# R_Box.net
KiCad netlist of a schematic drawn in Altium Designer
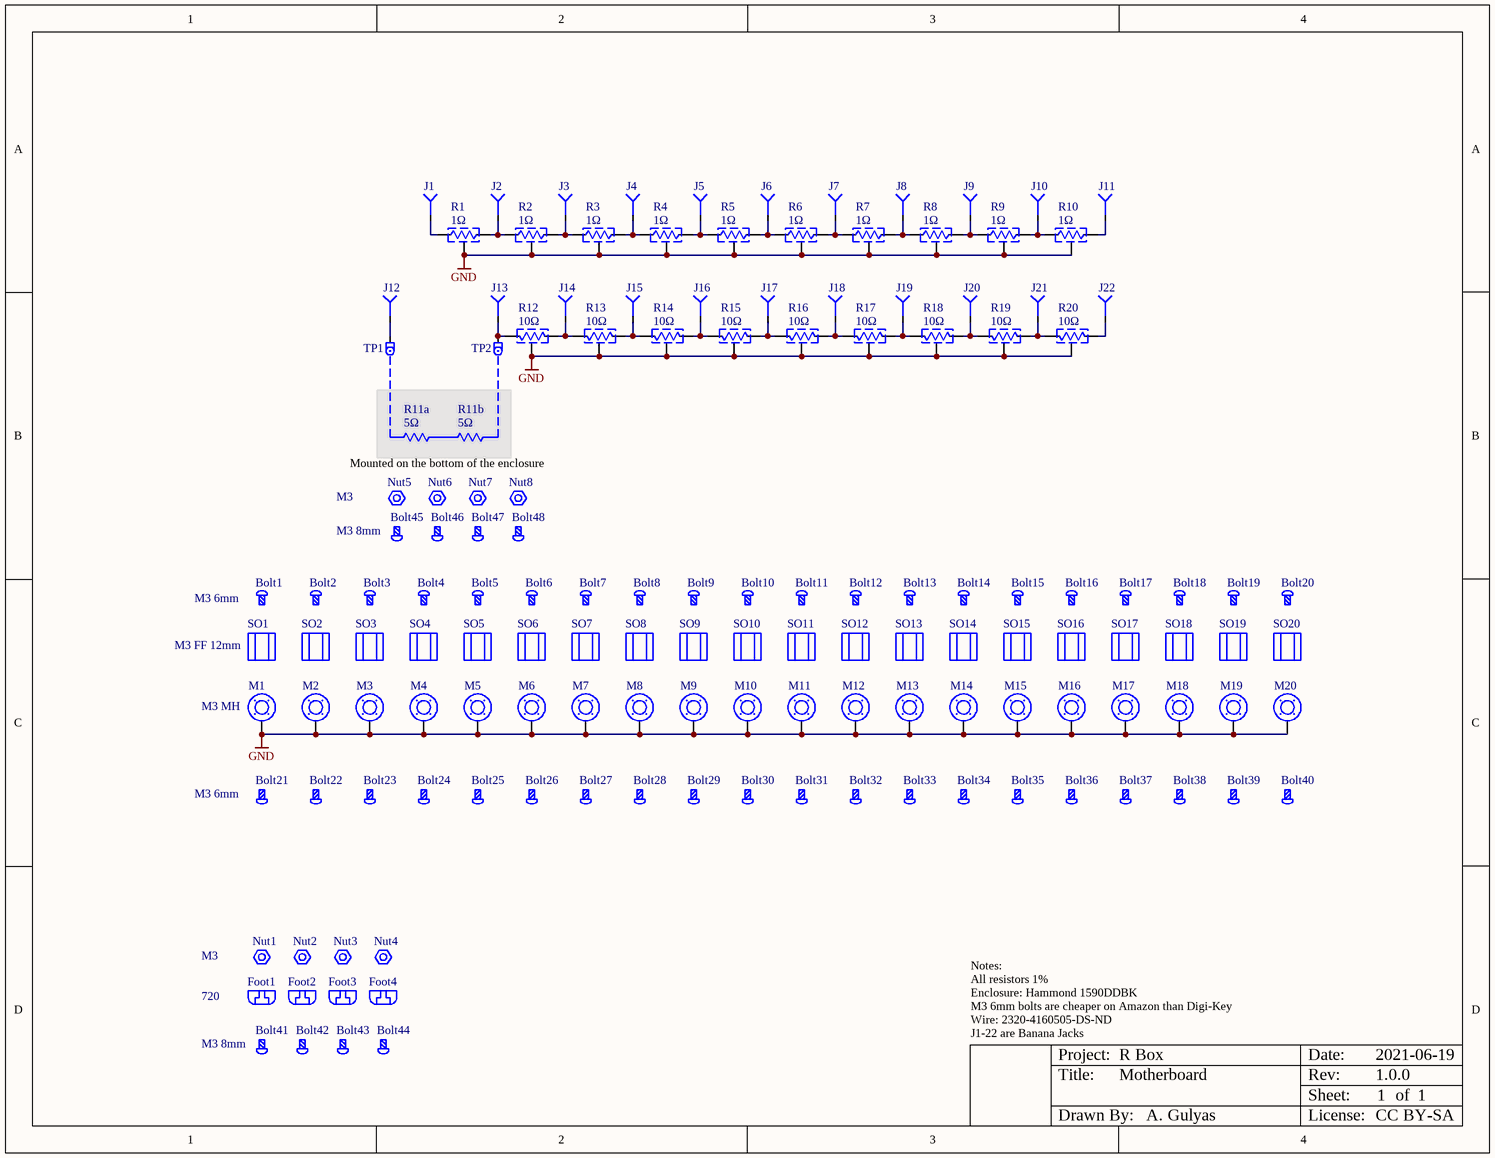
[diagram p0: R Box.SchDoc]

(export (version "E")
  (design (tool "Eeschema 10.0.6"))
  (components
    (comp (ref "Bolt1")
      (value "M3 6mm")
      (footprint "Mech - Bolt - M3 - 6mm")
      (description "MACH SCREW PAN HEAD PHILLIPS M3")
      (fields (field (name "MFG") "APM Hexseal"))
      (libsource (lib "Public Library") (part "Mech - Bolt - M3 - 6mm"))
    )
    (comp (ref "Bolt2")
      (value "M3 6mm")
      (footprint "Mech - Bolt - M3 - 6mm")
      (description "MACH SCREW PAN HEAD PHILLIPS M3")
      (fields (field (name "MFG") "APM Hexseal"))
      (libsource (lib "Public Library") (part "Mech - Bolt - M3 - 6mm"))
    )
    (comp (ref "Bolt3")
      (value "M3 6mm")
      (footprint "Mech - Bolt - M3 - 6mm")
      (description "MACH SCREW PAN HEAD PHILLIPS M3")
      (fields (field (name "MFG") "APM Hexseal"))
      (libsource (lib "Public Library") (part "Mech - Bolt - M3 - 6mm"))
    )
    (comp (ref "Bolt4")
      (value "M3 6mm")
      (footprint "Mech - Bolt - M3 - 6mm")
      (description "MACH SCREW PAN HEAD PHILLIPS M3")
      (fields (field (name "MFG") "APM Hexseal"))
      (libsource (lib "Public Library") (part "Mech - Bolt - M3 - 6mm"))
    )
    (comp (ref "Bolt5")
      (value "M3 6mm")
      (footprint "Mech - Bolt - M3 - 6mm")
      (description "MACH SCREW PAN HEAD PHILLIPS M3")
      (fields (field (name "MFG") "APM Hexseal"))
      (libsource (lib "Public Library") (part "Mech - Bolt - M3 - 6mm"))
    )
    (comp (ref "Bolt6")
      (value "M3 6mm")
      (footprint "Mech - Bolt - M3 - 6mm")
      (description "MACH SCREW PAN HEAD PHILLIPS M3")
      (fields (field (name "MFG") "APM Hexseal"))
      (libsource (lib "Public Library") (part "Mech - Bolt - M3 - 6mm"))
    )
    (comp (ref "Bolt7")
      (value "M3 6mm")
      (footprint "Mech - Bolt - M3 - 6mm")
      (description "MACH SCREW PAN HEAD PHILLIPS M3")
      (fields (field (name "MFG") "APM Hexseal"))
      (libsource (lib "Public Library") (part "Mech - Bolt - M3 - 6mm"))
    )
    (comp (ref "Bolt8")
      (value "M3 6mm")
      (footprint "Mech - Bolt - M3 - 6mm")
      (description "MACH SCREW PAN HEAD PHILLIPS M3")
      (fields (field (name "MFG") "APM Hexseal"))
      (libsource (lib "Public Library") (part "Mech - Bolt - M3 - 6mm"))
    )
    (comp (ref "Bolt9")
      (value "M3 6mm")
      (footprint "Mech - Bolt - M3 - 6mm")
      (description "MACH SCREW PAN HEAD PHILLIPS M3")
      (fields (field (name "MFG") "APM Hexseal"))
      (libsource (lib "Public Library") (part "Mech - Bolt - M3 - 6mm"))
    )
    (comp (ref "Bolt10")
      (value "M3 6mm")
      (footprint "Mech - Bolt - M3 - 6mm")
      (description "MACH SCREW PAN HEAD PHILLIPS M3")
      (fields (field (name "MFG") "APM Hexseal"))
      (libsource (lib "Public Library") (part "Mech - Bolt - M3 - 6mm"))
    )
    (comp (ref "Bolt11")
      (value "M3 6mm")
      (footprint "Mech - Bolt - M3 - 6mm")
      (description "MACH SCREW PAN HEAD PHILLIPS M3")
      (fields (field (name "MFG") "APM Hexseal"))
      (libsource (lib "Public Library") (part "Mech - Bolt - M3 - 6mm"))
    )
    (comp (ref "Bolt12")
      (value "M3 6mm")
      (footprint "Mech - Bolt - M3 - 6mm")
      (description "MACH SCREW PAN HEAD PHILLIPS M3")
      (fields (field (name "MFG") "APM Hexseal"))
      (libsource (lib "Public Library") (part "Mech - Bolt - M3 - 6mm"))
    )
    (comp (ref "Bolt13")
      (value "M3 6mm")
      (footprint "Mech - Bolt - M3 - 6mm")
      (description "MACH SCREW PAN HEAD PHILLIPS M3")
      (fields (field (name "MFG") "APM Hexseal"))
      (libsource (lib "Public Library") (part "Mech - Bolt - M3 - 6mm"))
    )
    (comp (ref "Bolt14")
      (value "M3 6mm")
      (footprint "Mech - Bolt - M3 - 6mm")
      (description "MACH SCREW PAN HEAD PHILLIPS M3")
      (fields (field (name "MFG") "APM Hexseal"))
      (libsource (lib "Public Library") (part "Mech - Bolt - M3 - 6mm"))
    )
    (comp (ref "Bolt15")
      (value "M3 6mm")
      (footprint "Mech - Bolt - M3 - 6mm")
      (description "MACH SCREW PAN HEAD PHILLIPS M3")
      (fields (field (name "MFG") "APM Hexseal"))
      (libsource (lib "Public Library") (part "Mech - Bolt - M3 - 6mm"))
    )
    (comp (ref "Bolt16")
      (value "M3 6mm")
      (footprint "Mech - Bolt - M3 - 6mm")
      (description "MACH SCREW PAN HEAD PHILLIPS M3")
      (fields (field (name "MFG") "APM Hexseal"))
      (libsource (lib "Public Library") (part "Mech - Bolt - M3 - 6mm"))
    )
    (comp (ref "Bolt17")
      (value "M3 6mm")
      (footprint "Mech - Bolt - M3 - 6mm")
      (description "MACH SCREW PAN HEAD PHILLIPS M3")
      (fields (field (name "MFG") "APM Hexseal"))
      (libsource (lib "Public Library") (part "Mech - Bolt - M3 - 6mm"))
    )
    (comp (ref "Bolt18")
      (value "M3 6mm")
      (footprint "Mech - Bolt - M3 - 6mm")
      (description "MACH SCREW PAN HEAD PHILLIPS M3")
      (fields (field (name "MFG") "APM Hexseal"))
      (libsource (lib "Public Library") (part "Mech - Bolt - M3 - 6mm"))
    )
    (comp (ref "Bolt19")
      (value "M3 6mm")
      (footprint "Mech - Bolt - M3 - 6mm")
      (description "MACH SCREW PAN HEAD PHILLIPS M3")
      (fields (field (name "MFG") "APM Hexseal"))
      (libsource (lib "Public Library") (part "Mech - Bolt - M3 - 6mm"))
    )
    (comp (ref "Bolt20")
      (value "M3 6mm")
      (footprint "Mech - Bolt - M3 - 6mm")
      (description "MACH SCREW PAN HEAD PHILLIPS M3")
      (fields (field (name "MFG") "APM Hexseal"))
      (libsource (lib "Public Library") (part "Mech - Bolt - M3 - 6mm"))
    )
    (comp (ref "Bolt21")
      (value "M3 6mm")
      (footprint "Mech - Bolt - M3 - 6mm - back")
      (description "MACH SCREW PAN HEAD PHILLIPS M3")
      (fields (field (name "MFG") "APM Hexseal"))
      (libsource (lib "") (part "Mech - Bolt - M3 - 6mm_1"))
    )
    (comp (ref "Bolt22")
      (value "M3 6mm")
      (footprint "Mech - Bolt - M3 - 6mm - back")
      (description "MACH SCREW PAN HEAD PHILLIPS M3")
      (fields (field (name "MFG") "APM Hexseal"))
      (libsource (lib "") (part "Mech - Bolt - M3 - 6mm_1"))
    )
    (comp (ref "Bolt23")
      (value "M3 6mm")
      (footprint "Mech - Bolt - M3 - 6mm - back")
      (description "MACH SCREW PAN HEAD PHILLIPS M3")
      (fields (field (name "MFG") "APM Hexseal"))
      (libsource (lib "") (part "Mech - Bolt - M3 - 6mm_1"))
    )
    (comp (ref "Bolt24")
      (value "M3 6mm")
      (footprint "Mech - Bolt - M3 - 6mm - back")
      (description "MACH SCREW PAN HEAD PHILLIPS M3")
      (fields (field (name "MFG") "APM Hexseal"))
      (libsource (lib "") (part "Mech - Bolt - M3 - 6mm_1"))
    )
    (comp (ref "Bolt25")
      (value "M3 6mm")
      (footprint "Mech - Bolt - M3 - 6mm - back")
      (description "MACH SCREW PAN HEAD PHILLIPS M3")
      (fields (field (name "MFG") "APM Hexseal"))
      (libsource (lib "") (part "Mech - Bolt - M3 - 6mm_1"))
    )
    (comp (ref "Bolt26")
      (value "M3 6mm")
      (footprint "Mech - Bolt - M3 - 6mm - back")
      (description "MACH SCREW PAN HEAD PHILLIPS M3")
      (fields (field (name "MFG") "APM Hexseal"))
      (libsource (lib "") (part "Mech - Bolt - M3 - 6mm_1"))
    )
    (comp (ref "Bolt27")
      (value "M3 6mm")
      (footprint "Mech - Bolt - M3 - 6mm - back")
      (description "MACH SCREW PAN HEAD PHILLIPS M3")
      (fields (field (name "MFG") "APM Hexseal"))
      (libsource (lib "") (part "Mech - Bolt - M3 - 6mm_1"))
    )
    (comp (ref "Bolt28")
      (value "M3 6mm")
      (footprint "Mech - Bolt - M3 - 6mm - back")
      (description "MACH SCREW PAN HEAD PHILLIPS M3")
      (fields (field (name "MFG") "APM Hexseal"))
      (libsource (lib "") (part "Mech - Bolt - M3 - 6mm_1"))
    )
    (comp (ref "Bolt29")
      (value "M3 6mm")
      (footprint "Mech - Bolt - M3 - 6mm - back")
      (description "MACH SCREW PAN HEAD PHILLIPS M3")
      (fields (field (name "MFG") "APM Hexseal"))
      (libsource (lib "") (part "Mech - Bolt - M3 - 6mm_1"))
    )
    (comp (ref "Bolt30")
      (value "M3 6mm")
      (footprint "Mech - Bolt - M3 - 6mm - back")
      (description "MACH SCREW PAN HEAD PHILLIPS M3")
      (fields (field (name "MFG") "APM Hexseal"))
      (libsource (lib "") (part "Mech - Bolt - M3 - 6mm_1"))
    )
    (comp (ref "Bolt31")
      (value "M3 6mm")
      (footprint "Mech - Bolt - M3 - 6mm - back")
      (description "MACH SCREW PAN HEAD PHILLIPS M3")
      (fields (field (name "MFG") "APM Hexseal"))
      (libsource (lib "") (part "Mech - Bolt - M3 - 6mm_1"))
    )
    (comp (ref "Bolt32")
      (value "M3 6mm")
      (footprint "Mech - Bolt - M3 - 6mm - back")
      (description "MACH SCREW PAN HEAD PHILLIPS M3")
      (fields (field (name "MFG") "APM Hexseal"))
      (libsource (lib "") (part "Mech - Bolt - M3 - 6mm_1"))
    )
    (comp (ref "Bolt33")
      (value "M3 6mm")
      (footprint "Mech - Bolt - M3 - 6mm - back")
      (description "MACH SCREW PAN HEAD PHILLIPS M3")
      (fields (field (name "MFG") "APM Hexseal"))
      (libsource (lib "") (part "Mech - Bolt - M3 - 6mm_1"))
    )
    (comp (ref "Bolt34")
      (value "M3 6mm")
      (footprint "Mech - Bolt - M3 - 6mm - back")
      (description "MACH SCREW PAN HEAD PHILLIPS M3")
      (fields (field (name "MFG") "APM Hexseal"))
      (libsource (lib "") (part "Mech - Bolt - M3 - 6mm_1"))
    )
    (comp (ref "Bolt35")
      (value "M3 6mm")
      (footprint "Mech - Bolt - M3 - 6mm - back")
      (description "MACH SCREW PAN HEAD PHILLIPS M3")
      (fields (field (name "MFG") "APM Hexseal"))
      (libsource (lib "") (part "Mech - Bolt - M3 - 6mm_1"))
    )
    (comp (ref "Bolt36")
      (value "M3 6mm")
      (footprint "Mech - Bolt - M3 - 6mm - back")
      (description "MACH SCREW PAN HEAD PHILLIPS M3")
      (fields (field (name "MFG") "APM Hexseal"))
      (libsource (lib "") (part "Mech - Bolt - M3 - 6mm_1"))
    )
    (comp (ref "Bolt37")
      (value "M3 6mm")
      (footprint "Mech - Bolt - M3 - 6mm - back")
      (description "MACH SCREW PAN HEAD PHILLIPS M3")
      (fields (field (name "MFG") "APM Hexseal"))
      (libsource (lib "") (part "Mech - Bolt - M3 - 6mm_1"))
    )
    (comp (ref "Bolt38")
      (value "M3 6mm")
      (footprint "Mech - Bolt - M3 - 6mm - back")
      (description "MACH SCREW PAN HEAD PHILLIPS M3")
      (fields (field (name "MFG") "APM Hexseal"))
      (libsource (lib "") (part "Mech - Bolt - M3 - 6mm_1"))
    )
    (comp (ref "Bolt39")
      (value "M3 6mm")
      (footprint "Mech - Bolt - M3 - 6mm - back")
      (description "MACH SCREW PAN HEAD PHILLIPS M3")
      (fields (field (name "MFG") "APM Hexseal"))
      (libsource (lib "") (part "Mech - Bolt - M3 - 6mm_1"))
    )
    (comp (ref "Bolt40")
      (value "M3 6mm")
      (footprint "Mech - Bolt - M3 - 6mm - back")
      (description "MACH SCREW PAN HEAD PHILLIPS M3")
      (fields (field (name "MFG") "APM Hexseal"))
      (libsource (lib "") (part "Mech - Bolt - M3 - 6mm_1"))
    )
    (comp (ref "Bolt41")
      (value "M3 8mm")
      (footprint "Mech - Bolt - M3 - 8mm")
      (description "MACH SCREW PAN HEAD PHILLIPS M3")
      (fields (field (name "MFG") "B&F Fastener Supply"))
      (libsource (lib "Public Library") (part "Mech - Bolt - M3 - 8mm"))
    )
    (comp (ref "Bolt42")
      (value "M3 8mm")
      (footprint "Mech - Bolt - M3 - 8mm")
      (description "MACH SCREW PAN HEAD PHILLIPS M3")
      (fields (field (name "MFG") "B&F Fastener Supply"))
      (libsource (lib "Public Library") (part "Mech - Bolt - M3 - 8mm"))
    )
    (comp (ref "Bolt43")
      (value "M3 8mm")
      (footprint "Mech - Bolt - M3 - 8mm")
      (description "MACH SCREW PAN HEAD PHILLIPS M3")
      (fields (field (name "MFG") "B&F Fastener Supply"))
      (libsource (lib "Public Library") (part "Mech - Bolt - M3 - 8mm"))
    )
    (comp (ref "Bolt44")
      (value "M3 8mm")
      (footprint "Mech - Bolt - M3 - 8mm")
      (description "MACH SCREW PAN HEAD PHILLIPS M3")
      (fields (field (name "MFG") "B&F Fastener Supply"))
      (libsource (lib "Public Library") (part "Mech - Bolt - M3 - 8mm"))
    )
    (comp (ref "Bolt45")
      (value "M3 8mm")
      (footprint "Mech - Bolt - M3 - 8mm")
      (description "MACH SCREW PAN HEAD PHILLIPS M3")
      (fields (field (name "MFG") "B&F Fastener Supply"))
      (libsource (lib "Public Library") (part "Mech - Bolt - M3 - 8mm"))
    )
    (comp (ref "Bolt46")
      (value "M3 8mm")
      (footprint "Mech - Bolt - M3 - 8mm")
      (description "MACH SCREW PAN HEAD PHILLIPS M3")
      (fields (field (name "MFG") "B&F Fastener Supply"))
      (libsource (lib "Public Library") (part "Mech - Bolt - M3 - 8mm"))
    )
    (comp (ref "Bolt47")
      (value "M3 8mm")
      (footprint "Mech - Bolt - M3 - 8mm")
      (description "MACH SCREW PAN HEAD PHILLIPS M3")
      (fields (field (name "MFG") "B&F Fastener Supply"))
      (libsource (lib "Public Library") (part "Mech - Bolt - M3 - 8mm"))
    )
    (comp (ref "Bolt48")
      (value "M3 8mm")
      (footprint "Mech - Bolt - M3 - 8mm")
      (description "MACH SCREW PAN HEAD PHILLIPS M3")
      (fields (field (name "MFG") "B&F Fastener Supply"))
      (libsource (lib "Public Library") (part "Mech - Bolt - M3 - 8mm"))
    )
    (comp (ref "Foot1")
      (value "720")
      (footprint "Feet - M3 - PN720")
      (description "BUMPER CYLINDRICAL 0.5\" DIA BLK")
      (fields (field (name "MFG") "Keystone Electronics"))
      (libsource (lib "Public Library") (part "Feet - M3 - 720"))
    )
    (comp (ref "Foot2")
      (value "720")
      (footprint "Feet - M3 - PN720")
      (description "BUMPER CYLINDRICAL 0.5\" DIA BLK")
      (fields (field (name "MFG") "Keystone Electronics"))
      (libsource (lib "Public Library") (part "Feet - M3 - 720"))
    )
    (comp (ref "Foot3")
      (value "720")
      (footprint "Feet - M3 - PN720")
      (description "BUMPER CYLINDRICAL 0.5\" DIA BLK")
      (fields (field (name "MFG") "Keystone Electronics"))
      (libsource (lib "Public Library") (part "Feet - M3 - 720"))
    )
    (comp (ref "Foot4")
      (value "720")
      (footprint "Feet - M3 - PN720")
      (description "BUMPER CYLINDRICAL 0.5\" DIA BLK")
      (fields (field (name "MFG") "Keystone Electronics"))
      (libsource (lib "Public Library") (part "Feet - M3 - 720"))
    )
    (comp (ref "J1")
      (value "Banana")
      (footprint "J - Banana - 108-09xx series")
      (description "CONN BANANA JACK SLDR TABS GREEN")
      (fields (field (name "MFG") "Cinch Connectivity Solutions Johnson"))
      (libsource (lib "Public Library") (part "Jack - Banana - 108-0904-001"))
    )
    (comp (ref "J2")
      (value "Banana")
      (footprint "J - Banana - 108-09xx series")
      (description "CONN BANANA JACK SLDR TABS GREEN")
      (fields (field (name "MFG") "Cinch Connectivity Solutions Johnson"))
      (libsource (lib "Public Library") (part "Jack - Banana - 108-0904-001"))
    )
    (comp (ref "J3")
      (value "Banana")
      (footprint "J - Banana - 108-09xx series")
      (description "CONN BANANA JACK SLDR TABS GREEN")
      (fields (field (name "MFG") "Cinch Connectivity Solutions Johnson"))
      (libsource (lib "Public Library") (part "Jack - Banana - 108-0904-001"))
    )
    (comp (ref "J4")
      (value "Banana")
      (footprint "J - Banana - 108-09xx series")
      (description "CONN BANANA JACK SLDR TABS GREEN")
      (fields (field (name "MFG") "Cinch Connectivity Solutions Johnson"))
      (libsource (lib "Public Library") (part "Jack - Banana - 108-0904-001"))
    )
    (comp (ref "J5")
      (value "Banana")
      (footprint "J - Banana - 108-09xx series")
      (description "CONN BANANA JACK SLDR TABS GREEN")
      (fields (field (name "MFG") "Cinch Connectivity Solutions Johnson"))
      (libsource (lib "Public Library") (part "Jack - Banana - 108-0904-001"))
    )
    (comp (ref "J6")
      (value "Banana")
      (footprint "J - Banana - 108-09xx series")
      (description "CONN BANANA JACK SLDR TABS GREEN")
      (fields (field (name "MFG") "Cinch Connectivity Solutions Johnson"))
      (libsource (lib "Public Library") (part "Jack - Banana - 108-0904-001"))
    )
    (comp (ref "J7")
      (value "Banana")
      (footprint "J - Banana - 108-09xx series")
      (description "CONN BANANA JACK SLDR TABS GREEN")
      (fields (field (name "MFG") "Cinch Connectivity Solutions Johnson"))
      (libsource (lib "Public Library") (part "Jack - Banana - 108-0904-001"))
    )
    (comp (ref "J8")
      (value "Banana")
      (footprint "J - Banana - 108-09xx series")
      (description "CONN BANANA JACK SLDR TABS GREEN")
      (fields (field (name "MFG") "Cinch Connectivity Solutions Johnson"))
      (libsource (lib "Public Library") (part "Jack - Banana - 108-0904-001"))
    )
    (comp (ref "J9")
      (value "Banana")
      (footprint "J - Banana - 108-09xx series")
      (description "CONN BANANA JACK SLDR TABS GREEN")
      (fields (field (name "MFG") "Cinch Connectivity Solutions Johnson"))
      (libsource (lib "Public Library") (part "Jack - Banana - 108-0904-001"))
    )
    (comp (ref "J10")
      (value "Banana")
      (footprint "J - Banana - 108-09xx series")
      (description "CONN BANANA JACK SLDR TABS GREEN")
      (fields (field (name "MFG") "Cinch Connectivity Solutions Johnson"))
      (libsource (lib "Public Library") (part "Jack - Banana - 108-0904-001"))
    )
    (comp (ref "J11")
      (value "Banana")
      (footprint "J - Banana - 108-09xx series")
      (description "CONN BANANA JACK SLDR TABS GREEN")
      (fields (field (name "MFG") "Cinch Connectivity Solutions Johnson"))
      (libsource (lib "Public Library") (part "Jack - Banana - 108-0904-001"))
    )
    (comp (ref "J12")
      (value "Banana")
      (footprint "J - Banana - 108-09xx series")
      (description "CONN BANANA JACK SLDR TABS GREEN")
      (fields (field (name "MFG") "Cinch Connectivity Solutions Johnson"))
      (libsource (lib "Public Library") (part "Jack - Banana - 108-0904-001"))
    )
    (comp (ref "J13")
      (value "Banana")
      (footprint "J - Banana - 108-09xx series")
      (description "CONN BANANA JACK SLDR TABS GREEN")
      (fields (field (name "MFG") "Cinch Connectivity Solutions Johnson"))
      (libsource (lib "Public Library") (part "Jack - Banana - 108-0904-001"))
    )
    (comp (ref "J14")
      (value "Banana")
      (footprint "J - Banana - 108-09xx series")
      (description "CONN BANANA JACK SLDR TABS GREEN")
      (fields (field (name "MFG") "Cinch Connectivity Solutions Johnson"))
      (libsource (lib "Public Library") (part "Jack - Banana - 108-0904-001"))
    )
    (comp (ref "J15")
      (value "Banana")
      (footprint "J - Banana - 108-09xx series")
      (description "CONN BANANA JACK SLDR TABS GREEN")
      (fields (field (name "MFG") "Cinch Connectivity Solutions Johnson"))
      (libsource (lib "Public Library") (part "Jack - Banana - 108-0904-001"))
    )
    (comp (ref "J16")
      (value "Banana")
      (footprint "J - Banana - 108-09xx series")
      (description "CONN BANANA JACK SLDR TABS GREEN")
      (fields (field (name "MFG") "Cinch Connectivity Solutions Johnson"))
      (libsource (lib "Public Library") (part "Jack - Banana - 108-0904-001"))
    )
    (comp (ref "J17")
      (value "Banana")
      (footprint "J - Banana - 108-09xx series")
      (description "CONN BANANA JACK SLDR TABS GREEN")
      (fields (field (name "MFG") "Cinch Connectivity Solutions Johnson"))
      (libsource (lib "Public Library") (part "Jack - Banana - 108-0904-001"))
    )
    (comp (ref "J18")
      (value "Banana")
      (footprint "J - Banana - 108-09xx series")
      (description "CONN BANANA JACK SLDR TABS GREEN")
      (fields (field (name "MFG") "Cinch Connectivity Solutions Johnson"))
      (libsource (lib "Public Library") (part "Jack - Banana - 108-0904-001"))
    )
    (comp (ref "J19")
      (value "Banana")
      (footprint "J - Banana - 108-09xx series")
      (description "CONN BANANA JACK SLDR TABS GREEN")
      (fields (field (name "MFG") "Cinch Connectivity Solutions Johnson"))
      (libsource (lib "Public Library") (part "Jack - Banana - 108-0904-001"))
    )
    (comp (ref "J20")
      (value "Banana")
      (footprint "J - Banana - 108-09xx series")
      (description "CONN BANANA JACK SLDR TABS GREEN")
      (fields (field (name "MFG") "Cinch Connectivity Solutions Johnson"))
      (libsource (lib "Public Library") (part "Jack - Banana - 108-0904-001"))
    )
    (comp (ref "J21")
      (value "Banana")
      (footprint "J - Banana - 108-09xx series")
      (description "CONN BANANA JACK SLDR TABS GREEN")
      (fields (field (name "MFG") "Cinch Connectivity Solutions Johnson"))
      (libsource (lib "Public Library") (part "Jack - Banana - 108-0904-001"))
    )
    (comp (ref "J22")
      (value "Banana")
      (footprint "J - Banana - 108-09xx series")
      (description "CONN BANANA JACK SLDR TABS GREEN")
      (fields (field (name "MFG") "Cinch Connectivity Solutions Johnson"))
      (libsource (lib "Public Library") (part "Jack - Banana - 108-0904-001"))
    )
    (comp (ref "M1")
      (value "M3 MH")
      (footprint "Bolt Hole - M3")
      (description "M3 Mounting Pad")
      (libsource (lib "Public Library") (part "Mech - Bolt Hole - M3"))
    )
    (comp (ref "M2")
      (value "M3 MH")
      (footprint "Bolt Hole - M3")
      (description "M3 Mounting Pad")
      (libsource (lib "Public Library") (part "Mech - Bolt Hole - M3"))
    )
    (comp (ref "M3")
      (value "M3 MH")
      (footprint "Bolt Hole - M3")
      (description "M3 Mounting Pad")
      (libsource (lib "Public Library") (part "Mech - Bolt Hole - M3"))
    )
    (comp (ref "M4")
      (value "M3 MH")
      (footprint "Bolt Hole - M3")
      (description "M3 Mounting Pad")
      (libsource (lib "Public Library") (part "Mech - Bolt Hole - M3"))
    )
    (comp (ref "M5")
      (value "M3 MH")
      (footprint "Bolt Hole - M3")
      (description "M3 Mounting Pad")
      (libsource (lib "Public Library") (part "Mech - Bolt Hole - M3"))
    )
    (comp (ref "M6")
      (value "M3 MH")
      (footprint "Bolt Hole - M3")
      (description "M3 Mounting Pad")
      (libsource (lib "Public Library") (part "Mech - Bolt Hole - M3"))
    )
    (comp (ref "M7")
      (value "M3 MH")
      (footprint "Bolt Hole - M3")
      (description "M3 Mounting Pad")
      (libsource (lib "Public Library") (part "Mech - Bolt Hole - M3"))
    )
    (comp (ref "M8")
      (value "M3 MH")
      (footprint "Bolt Hole - M3")
      (description "M3 Mounting Pad")
      (libsource (lib "Public Library") (part "Mech - Bolt Hole - M3"))
    )
    (comp (ref "M9")
      (value "M3 MH")
      (footprint "Bolt Hole - M3")
      (description "M3 Mounting Pad")
      (libsource (lib "Public Library") (part "Mech - Bolt Hole - M3"))
    )
    (comp (ref "M10")
      (value "M3 MH")
      (footprint "Bolt Hole - M3")
      (description "M3 Mounting Pad")
      (libsource (lib "Public Library") (part "Mech - Bolt Hole - M3"))
    )
    (comp (ref "M11")
      (value "M3 MH")
      (footprint "Bolt Hole - M3")
      (description "M3 Mounting Pad")
      (libsource (lib "Public Library") (part "Mech - Bolt Hole - M3"))
    )
    (comp (ref "M12")
      (value "M3 MH")
      (footprint "Bolt Hole - M3")
      (description "M3 Mounting Pad")
      (libsource (lib "Public Library") (part "Mech - Bolt Hole - M3"))
    )
    (comp (ref "M13")
      (value "M3 MH")
      (footprint "Bolt Hole - M3")
      (description "M3 Mounting Pad")
      (libsource (lib "Public Library") (part "Mech - Bolt Hole - M3"))
    )
    (comp (ref "M14")
      (value "M3 MH")
      (footprint "Bolt Hole - M3")
      (description "M3 Mounting Pad")
      (libsource (lib "Public Library") (part "Mech - Bolt Hole - M3"))
    )
    (comp (ref "M15")
      (value "M3 MH")
      (footprint "Bolt Hole - M3")
      (description "M3 Mounting Pad")
      (libsource (lib "Public Library") (part "Mech - Bolt Hole - M3"))
    )
    (comp (ref "M16")
      (value "M3 MH")
      (footprint "Bolt Hole - M3")
      (description "M3 Mounting Pad")
      (libsource (lib "Public Library") (part "Mech - Bolt Hole - M3"))
    )
    (comp (ref "M17")
      (value "M3 MH")
      (footprint "Bolt Hole - M3")
      (description "M3 Mounting Pad")
      (libsource (lib "Public Library") (part "Mech - Bolt Hole - M3"))
    )
    (comp (ref "M18")
      (value "M3 MH")
      (footprint "Bolt Hole - M3")
      (description "M3 Mounting Pad")
      (libsource (lib "Public Library") (part "Mech - Bolt Hole - M3"))
    )
    (comp (ref "M19")
      (value "M3 MH")
      (footprint "Bolt Hole - M3")
      (description "M3 Mounting Pad")
      (libsource (lib "Public Library") (part "Mech - Bolt Hole - M3"))
    )
    (comp (ref "M20")
      (value "M3 MH")
      (footprint "Bolt Hole - M3")
      (description "M3 Mounting Pad")
      (libsource (lib "Public Library") (part "Mech - Bolt Hole - M3"))
    )
    (comp (ref "Nut1")
      (value "M3")
      (footprint "Mech - Nut - M3")
      (description "HEX NUT 0.217\" STEEL M3")
      (fields (field (name "MFG") "Keystone Electronics"))
      (libsource (lib "Public Library") (part "Mech - Nut - M3"))
    )
    (comp (ref "Nut2")
      (value "M3")
      (footprint "Mech - Nut - M3")
      (description "HEX NUT 0.217\" STEEL M3")
      (fields (field (name "MFG") "Keystone Electronics"))
      (libsource (lib "Public Library") (part "Mech - Nut - M3"))
    )
    (comp (ref "Nut3")
      (value "M3")
      (footprint "Mech - Nut - M3")
      (description "HEX NUT 0.217\" STEEL M3")
      (fields (field (name "MFG") "Keystone Electronics"))
      (libsource (lib "Public Library") (part "Mech - Nut - M3"))
    )
    (comp (ref "Nut4")
      (value "M3")
      (footprint "Mech - Nut - M3")
      (description "HEX NUT 0.217\" STEEL M3")
      (fields (field (name "MFG") "Keystone Electronics"))
      (libsource (lib "Public Library") (part "Mech - Nut - M3"))
    )
    (comp (ref "Nut5")
      (value "M3")
      (footprint "Mech - Nut - M3")
      (description "HEX NUT 0.217\" STEEL M3")
      (fields (field (name "MFG") "Keystone Electronics"))
      (libsource (lib "Public Library") (part "Mech - Nut - M3"))
    )
    (comp (ref "Nut6")
      (value "M3")
      (footprint "Mech - Nut - M3")
      (description "HEX NUT 0.217\" STEEL M3")
      (fields (field (name "MFG") "Keystone Electronics"))
      (libsource (lib "Public Library") (part "Mech - Nut - M3"))
    )
    (comp (ref "Nut7")
      (value "M3")
      (footprint "Mech - Nut - M3")
      (description "HEX NUT 0.217\" STEEL M3")
      (fields (field (name "MFG") "Keystone Electronics"))
      (libsource (lib "Public Library") (part "Mech - Nut - M3"))
    )
    (comp (ref "Nut8")
      (value "M3")
      (footprint "Mech - Nut - M3")
      (description "HEX NUT 0.217\" STEEL M3")
      (fields (field (name "MFG") "Keystone Electronics"))
      (libsource (lib "Public Library") (part "Mech - Nut - M3"))
    )
    (comp (ref "R1")
      (value "1Ω")
      (footprint "R - PWR163")
      (description "RES SMD 1 OHM 1% 25W DPAK")
      (fields (field (name "MFG") "Bourns Inc.") (field (name "POWER") "25W"))
      (libsource (lib "Public Library") (part "R - SMT - 1Ω - 25W"))
    )
    (comp (ref "R2")
      (value "1Ω")
      (footprint "R - PWR163")
      (description "RES SMD 1 OHM 1% 25W DPAK")
      (fields (field (name "MFG") "Bourns Inc.") (field (name "POWER") "25W"))
      (libsource (lib "Public Library") (part "R - SMT - 1Ω - 25W"))
    )
    (comp (ref "R3")
      (value "1Ω")
      (footprint "R - PWR163")
      (description "RES SMD 1 OHM 1% 25W DPAK")
      (fields (field (name "MFG") "Bourns Inc.") (field (name "POWER") "25W"))
      (libsource (lib "Public Library") (part "R - SMT - 1Ω - 25W"))
    )
    (comp (ref "R4")
      (value "1Ω")
      (footprint "R - PWR163")
      (description "RES SMD 1 OHM 1% 25W DPAK")
      (fields (field (name "MFG") "Bourns Inc.") (field (name "POWER") "25W"))
      (libsource (lib "Public Library") (part "R - SMT - 1Ω - 25W"))
    )
    (comp (ref "R5")
      (value "1Ω")
      (footprint "R - PWR163")
      (description "RES SMD 1 OHM 1% 25W DPAK")
      (fields (field (name "MFG") "Bourns Inc.") (field (name "POWER") "25W"))
      (libsource (lib "Public Library") (part "R - SMT - 1Ω - 25W"))
    )
    (comp (ref "R6")
      (value "1Ω")
      (footprint "R - PWR163")
      (description "RES SMD 1 OHM 1% 25W DPAK")
      (fields (field (name "MFG") "Bourns Inc.") (field (name "POWER") "25W"))
      (libsource (lib "Public Library") (part "R - SMT - 1Ω - 25W"))
    )
    (comp (ref "R7")
      (value "1Ω")
      (footprint "R - PWR163")
      (description "RES SMD 1 OHM 1% 25W DPAK")
      (fields (field (name "MFG") "Bourns Inc.") (field (name "POWER") "25W"))
      (libsource (lib "Public Library") (part "R - SMT - 1Ω - 25W"))
    )
    (comp (ref "R8")
      (value "1Ω")
      (footprint "R - PWR163")
      (description "RES SMD 1 OHM 1% 25W DPAK")
      (fields (field (name "MFG") "Bourns Inc.") (field (name "POWER") "25W"))
      (libsource (lib "Public Library") (part "R - SMT - 1Ω - 25W"))
    )
    (comp (ref "R9")
      (value "1Ω")
      (footprint "R - PWR163")
      (description "RES SMD 1 OHM 1% 25W DPAK")
      (fields (field (name "MFG") "Bourns Inc.") (field (name "POWER") "25W"))
      (libsource (lib "Public Library") (part "R - SMT - 1Ω - 25W"))
    )
    (comp (ref "R10")
      (value "1Ω")
      (footprint "R - PWR163")
      (description "RES SMD 1 OHM 1% 25W DPAK")
      (fields (field (name "MFG") "Bourns Inc.") (field (name "POWER") "25W"))
      (libsource (lib "Public Library") (part "R - SMT - 1Ω - 25W"))
    )
    (comp (ref "R11a")
      (value "5Ω")
      (footprint "R - KAL50W")
      (description "RES CHAS MNT 5 OHM 1% 50W")
      (fields (field (name "MFG") "Stackpole Electronics Inc") (field (name "POWER") "50W"))
      (libsource (lib "Public Library") (part "R - PWR - 5Ω"))
    )
    (comp (ref "R11b")
      (value "5Ω")
      (footprint "R - KAL50W")
      (description "RES CHAS MNT 5 OHM 1% 50W")
      (fields (field (name "MFG") "Stackpole Electronics Inc") (field (name "POWER") "50W"))
      (libsource (lib "Public Library") (part "R - PWR - 5Ω"))
    )
    (comp (ref "R12")
      (value "10Ω")
      (footprint "R - PWR163")
      (description "RES SMD 10 OHM 1% 25W DPAK")
      (fields (field (name "MFG") "Bourns Inc.") (field (name "POWER") "25W"))
      (libsource (lib "Public Library") (part "R - SMT - 10Ω - 25W"))
    )
    (comp (ref "R13")
      (value "10Ω")
      (footprint "R - PWR163")
      (description "RES SMD 10 OHM 1% 25W DPAK")
      (fields (field (name "MFG") "Bourns Inc.") (field (name "POWER") "25W"))
      (libsource (lib "Public Library") (part "R - SMT - 10Ω - 25W"))
    )
    (comp (ref "R14")
      (value "10Ω")
      (footprint "R - PWR163")
      (description "RES SMD 10 OHM 1% 25W DPAK")
      (fields (field (name "MFG") "Bourns Inc.") (field (name "POWER") "25W"))
      (libsource (lib "Public Library") (part "R - SMT - 10Ω - 25W"))
    )
    (comp (ref "R15")
      (value "10Ω")
      (footprint "R - PWR163")
      (description "RES SMD 10 OHM 1% 25W DPAK")
      (fields (field (name "MFG") "Bourns Inc.") (field (name "POWER") "25W"))
      (libsource (lib "Public Library") (part "R - SMT - 10Ω - 25W"))
    )
    (comp (ref "R16")
      (value "10Ω")
      (footprint "R - PWR163")
      (description "RES SMD 10 OHM 1% 25W DPAK")
      (fields (field (name "MFG") "Bourns Inc.") (field (name "POWER") "25W"))
      (libsource (lib "Public Library") (part "R - SMT - 10Ω - 25W"))
    )
    (comp (ref "R17")
      (value "10Ω")
      (footprint "R - PWR163")
      (description "RES SMD 10 OHM 1% 25W DPAK")
      (fields (field (name "MFG") "Bourns Inc.") (field (name "POWER") "25W"))
      (libsource (lib "Public Library") (part "R - SMT - 10Ω - 25W"))
    )
    (comp (ref "R18")
      (value "10Ω")
      (footprint "R - PWR163")
      (description "RES SMD 10 OHM 1% 25W DPAK")
      (fields (field (name "MFG") "Bourns Inc.") (field (name "POWER") "25W"))
      (libsource (lib "Public Library") (part "R - SMT - 10Ω - 25W"))
    )
    (comp (ref "R19")
      (value "10Ω")
      (footprint "R - PWR163")
      (description "RES SMD 10 OHM 1% 25W DPAK")
      (fields (field (name "MFG") "Bourns Inc.") (field (name "POWER") "25W"))
      (libsource (lib "Public Library") (part "R - SMT - 10Ω - 25W"))
    )
    (comp (ref "R20")
      (value "10Ω")
      (footprint "R - PWR163")
      (description "RES SMD 10 OHM 1% 25W DPAK")
      (fields (field (name "MFG") "Bourns Inc.") (field (name "POWER") "25W"))
      (libsource (lib "Public Library") (part "R - SMT - 10Ω - 25W"))
    )
    (comp (ref "SO1")
      (value "M3 FF 12mm")
      (footprint "Mech - SO - M3 - FF - 12mm")
      (description "HEX STANDOFF M3 ALUMINUM 12MM")
      (fields (field (name "MFG") "Keystone Electronics"))
      (libsource (lib "Public Library") (part "Mech - SO - M3 - FF - 12mm"))
    )
    (comp (ref "SO2")
      (value "M3 FF 12mm")
      (footprint "Mech - SO - M3 - FF - 12mm")
      (description "HEX STANDOFF M3 ALUMINUM 12MM")
      (fields (field (name "MFG") "Keystone Electronics"))
      (libsource (lib "Public Library") (part "Mech - SO - M3 - FF - 12mm"))
    )
    (comp (ref "SO3")
      (value "M3 FF 12mm")
      (footprint "Mech - SO - M3 - FF - 12mm")
      (description "HEX STANDOFF M3 ALUMINUM 12MM")
      (fields (field (name "MFG") "Keystone Electronics"))
      (libsource (lib "Public Library") (part "Mech - SO - M3 - FF - 12mm"))
    )
    (comp (ref "SO4")
      (value "M3 FF 12mm")
      (footprint "Mech - SO - M3 - FF - 12mm")
      (description "HEX STANDOFF M3 ALUMINUM 12MM")
      (fields (field (name "MFG") "Keystone Electronics"))
      (libsource (lib "Public Library") (part "Mech - SO - M3 - FF - 12mm"))
    )
    (comp (ref "SO5")
      (value "M3 FF 12mm")
      (footprint "Mech - SO - M3 - FF - 12mm")
      (description "HEX STANDOFF M3 ALUMINUM 12MM")
      (fields (field (name "MFG") "Keystone Electronics"))
      (libsource (lib "Public Library") (part "Mech - SO - M3 - FF - 12mm"))
    )
    (comp (ref "SO6")
      (value "M3 FF 12mm")
      (footprint "Mech - SO - M3 - FF - 12mm")
      (description "HEX STANDOFF M3 ALUMINUM 12MM")
      (fields (field (name "MFG") "Keystone Electronics"))
      (libsource (lib "Public Library") (part "Mech - SO - M3 - FF - 12mm"))
    )
    (comp (ref "SO7")
      (value "M3 FF 12mm")
      (footprint "Mech - SO - M3 - FF - 12mm")
      (description "HEX STANDOFF M3 ALUMINUM 12MM")
      (fields (field (name "MFG") "Keystone Electronics"))
      (libsource (lib "Public Library") (part "Mech - SO - M3 - FF - 12mm"))
    )
    (comp (ref "SO8")
      (value "M3 FF 12mm")
      (footprint "Mech - SO - M3 - FF - 12mm")
      (description "HEX STANDOFF M3 ALUMINUM 12MM")
      (fields (field (name "MFG") "Keystone Electronics"))
      (libsource (lib "Public Library") (part "Mech - SO - M3 - FF - 12mm"))
    )
    (comp (ref "SO9")
      (value "M3 FF 12mm")
      (footprint "Mech - SO - M3 - FF - 12mm")
      (description "HEX STANDOFF M3 ALUMINUM 12MM")
      (fields (field (name "MFG") "Keystone Electronics"))
      (libsource (lib "Public Library") (part "Mech - SO - M3 - FF - 12mm"))
    )
    (comp (ref "SO10")
      (value "M3 FF 12mm")
      (footprint "Mech - SO - M3 - FF - 12mm")
      (description "HEX STANDOFF M3 ALUMINUM 12MM")
      (fields (field (name "MFG") "Keystone Electronics"))
      (libsource (lib "Public Library") (part "Mech - SO - M3 - FF - 12mm"))
    )
    (comp (ref "SO11")
      (value "M3 FF 12mm")
      (footprint "Mech - SO - M3 - FF - 12mm")
      (description "HEX STANDOFF M3 ALUMINUM 12MM")
      (fields (field (name "MFG") "Keystone Electronics"))
      (libsource (lib "Public Library") (part "Mech - SO - M3 - FF - 12mm"))
    )
    (comp (ref "SO12")
      (value "M3 FF 12mm")
      (footprint "Mech - SO - M3 - FF - 12mm")
      (description "HEX STANDOFF M3 ALUMINUM 12MM")
      (fields (field (name "MFG") "Keystone Electronics"))
      (libsource (lib "Public Library") (part "Mech - SO - M3 - FF - 12mm"))
    )
    (comp (ref "SO13")
      (value "M3 FF 12mm")
      (footprint "Mech - SO - M3 - FF - 12mm")
      (description "HEX STANDOFF M3 ALUMINUM 12MM")
      (fields (field (name "MFG") "Keystone Electronics"))
      (libsource (lib "Public Library") (part "Mech - SO - M3 - FF - 12mm"))
    )
    (comp (ref "SO14")
      (value "M3 FF 12mm")
      (footprint "Mech - SO - M3 - FF - 12mm")
      (description "HEX STANDOFF M3 ALUMINUM 12MM")
      (fields (field (name "MFG") "Keystone Electronics"))
      (libsource (lib "Public Library") (part "Mech - SO - M3 - FF - 12mm"))
    )
    (comp (ref "SO15")
      (value "M3 FF 12mm")
      (footprint "Mech - SO - M3 - FF - 12mm")
      (description "HEX STANDOFF M3 ALUMINUM 12MM")
      (fields (field (name "MFG") "Keystone Electronics"))
      (libsource (lib "Public Library") (part "Mech - SO - M3 - FF - 12mm"))
    )
    (comp (ref "SO16")
      (value "M3 FF 12mm")
      (footprint "Mech - SO - M3 - FF - 12mm")
      (description "HEX STANDOFF M3 ALUMINUM 12MM")
      (fields (field (name "MFG") "Keystone Electronics"))
      (libsource (lib "Public Library") (part "Mech - SO - M3 - FF - 12mm"))
    )
    (comp (ref "SO17")
      (value "M3 FF 12mm")
      (footprint "Mech - SO - M3 - FF - 12mm")
      (description "HEX STANDOFF M3 ALUMINUM 12MM")
      (fields (field (name "MFG") "Keystone Electronics"))
      (libsource (lib "Public Library") (part "Mech - SO - M3 - FF - 12mm"))
    )
    (comp (ref "SO18")
      (value "M3 FF 12mm")
      (footprint "Mech - SO - M3 - FF - 12mm")
      (description "HEX STANDOFF M3 ALUMINUM 12MM")
      (fields (field (name "MFG") "Keystone Electronics"))
      (libsource (lib "Public Library") (part "Mech - SO - M3 - FF - 12mm"))
    )
    (comp (ref "SO19")
      (value "M3 FF 12mm")
      (footprint "Mech - SO - M3 - FF - 12mm")
      (description "HEX STANDOFF M3 ALUMINUM 12MM")
      (fields (field (name "MFG") "Keystone Electronics"))
      (libsource (lib "Public Library") (part "Mech - SO - M3 - FF - 12mm"))
    )
    (comp (ref "SO20")
      (value "M3 FF 12mm")
      (footprint "Mech - SO - M3 - FF - 12mm")
      (description "HEX STANDOFF M3 ALUMINUM 12MM")
      (fields (field (name "MFG") "Keystone Electronics"))
      (libsource (lib "Public Library") (part "Mech - SO - M3 - FF - 12mm"))
    )
    (comp (ref "TP1")
      (value "Signal")
      (footprint "TP - TH - 4mm")
      (libsource (lib "Public Library") (part "TP - TH - 4mm"))
    )
    (comp (ref "TP2")
      (value "Signal")
      (footprint "TP - TH - 4mm")
      (libsource (lib "Public Library") (part "TP - TH - 4mm"))
    )
  )
  (nets
    (net (code "1") (name "GND") (class "Default")
      (node (ref "M1") (pin "1") (pinfunction "1_1") (pintype "passive"))
      (node (ref "M10") (pin "1") (pinfunction "1_1") (pintype "passive"))
      (node (ref "M11") (pin "1") (pinfunction "1_1") (pintype "passive"))
      (node (ref "M12") (pin "1") (pinfunction "1_1") (pintype "passive"))
      (node (ref "M13") (pin "1") (pinfunction "1_1") (pintype "passive"))
      (node (ref "M14") (pin "1") (pinfunction "1_1") (pintype "passive"))
      (node (ref "M15") (pin "1") (pinfunction "1_1") (pintype "passive"))
      (node (ref "M16") (pin "1") (pinfunction "1_1") (pintype "passive"))
      (node (ref "M17") (pin "1") (pinfunction "1_1") (pintype "passive"))
      (node (ref "M18") (pin "1") (pinfunction "1_1") (pintype "passive"))
      (node (ref "M19") (pin "1") (pinfunction "1_1") (pintype "passive"))
      (node (ref "M2") (pin "1") (pinfunction "1_1") (pintype "passive"))
      (node (ref "M20") (pin "1") (pinfunction "1_1") (pintype "passive"))
      (node (ref "M3") (pin "1") (pinfunction "1_1") (pintype "passive"))
      (node (ref "M4") (pin "1") (pinfunction "1_1") (pintype "passive"))
      (node (ref "M5") (pin "1") (pinfunction "1_1") (pintype "passive"))
      (node (ref "M6") (pin "1") (pinfunction "1_1") (pintype "passive"))
      (node (ref "M7") (pin "1") (pinfunction "1_1") (pintype "passive"))
      (node (ref "M8") (pin "1") (pinfunction "1_1") (pintype "passive"))
      (node (ref "M9") (pin "1") (pinfunction "1_1") (pintype "passive"))
      (node (ref "R1") (pin "0") (pinfunction "0_0") (pintype "passive"))
      (node (ref "R10") (pin "0") (pinfunction "0_0") (pintype "passive"))
      (node (ref "R12") (pin "0") (pinfunction "0_0") (pintype "passive"))
      (node (ref "R13") (pin "0") (pinfunction "0_0") (pintype "passive"))
      (node (ref "R14") (pin "0") (pinfunction "0_0") (pintype "passive"))
      (node (ref "R15") (pin "0") (pinfunction "0_0") (pintype "passive"))
      (node (ref "R16") (pin "0") (pinfunction "0_0") (pintype "passive"))
      (node (ref "R17") (pin "0") (pinfunction "0_0") (pintype "passive"))
      (node (ref "R18") (pin "0") (pinfunction "0_0") (pintype "passive"))
      (node (ref "R19") (pin "0") (pinfunction "0_0") (pintype "passive"))
      (node (ref "R2") (pin "0") (pinfunction "0_0") (pintype "passive"))
      (node (ref "R20") (pin "0") (pinfunction "0_0") (pintype "passive"))
      (node (ref "R3") (pin "0") (pinfunction "0_0") (pintype "passive"))
      (node (ref "R4") (pin "0") (pinfunction "0_0") (pintype "passive"))
      (node (ref "R5") (pin "0") (pinfunction "0_0") (pintype "passive"))
      (node (ref "R6") (pin "0") (pinfunction "0_0") (pintype "passive"))
      (node (ref "R7") (pin "0") (pinfunction "0_0") (pintype "passive"))
      (node (ref "R8") (pin "0") (pinfunction "0_0") (pintype "passive"))
      (node (ref "R9") (pin "0") (pinfunction "0_0") (pintype "passive"))
    )
    (net (code "2") (name "Net-(J1-Pad1)") (class "Default")
      (node (ref "J1") (pin "1") (pinfunction "1_1") (pintype "passive"))
      (node (ref "R1") (pin "1") (pinfunction "1_1") (pintype "passive"))
    )
    (net (code "3") (name "Net-(J2-Pad1)") (class "Default")
      (node (ref "J2") (pin "1") (pinfunction "1_1") (pintype "passive"))
      (node (ref "R1") (pin "2") (pinfunction "2_2") (pintype "passive"))
      (node (ref "R2") (pin "1") (pinfunction "1_1") (pintype "passive"))
    )
    (net (code "4") (name "Net-(J3-Pad1)") (class "Default")
      (node (ref "J3") (pin "1") (pinfunction "1_1") (pintype "passive"))
      (node (ref "R2") (pin "2") (pinfunction "2_2") (pintype "passive"))
      (node (ref "R3") (pin "1") (pinfunction "1_1") (pintype "passive"))
    )
    (net (code "5") (name "Net-(J4-Pad1)") (class "Default")
      (node (ref "J4") (pin "1") (pinfunction "1_1") (pintype "passive"))
      (node (ref "R3") (pin "2") (pinfunction "2_2") (pintype "passive"))
      (node (ref "R4") (pin "1") (pinfunction "1_1") (pintype "passive"))
    )
    (net (code "6") (name "Net-(J5-Pad1)") (class "Default")
      (node (ref "J5") (pin "1") (pinfunction "1_1") (pintype "passive"))
      (node (ref "R4") (pin "2") (pinfunction "2_2") (pintype "passive"))
      (node (ref "R5") (pin "1") (pinfunction "1_1") (pintype "passive"))
    )
    (net (code "7") (name "Net-(J6-Pad1)") (class "Default")
      (node (ref "J6") (pin "1") (pinfunction "1_1") (pintype "passive"))
      (node (ref "R5") (pin "2") (pinfunction "2_2") (pintype "passive"))
      (node (ref "R6") (pin "1") (pinfunction "1_1") (pintype "passive"))
    )
    (net (code "8") (name "Net-(J7-Pad1)") (class "Default")
      (node (ref "J7") (pin "1") (pinfunction "1_1") (pintype "passive"))
      (node (ref "R6") (pin "2") (pinfunction "2_2") (pintype "passive"))
      (node (ref "R7") (pin "1") (pinfunction "1_1") (pintype "passive"))
    )
    (net (code "9") (name "Net-(J8-Pad1)") (class "Default")
      (node (ref "J8") (pin "1") (pinfunction "1_1") (pintype "passive"))
      (node (ref "R7") (pin "2") (pinfunction "2_2") (pintype "passive"))
      (node (ref "R8") (pin "1") (pinfunction "1_1") (pintype "passive"))
    )
    (net (code "10") (name "Net-(J9-Pad1)") (class "Default")
      (node (ref "J9") (pin "1") (pinfunction "1_1") (pintype "passive"))
      (node (ref "R8") (pin "2") (pinfunction "2_2") (pintype "passive"))
      (node (ref "R9") (pin "1") (pinfunction "1_1") (pintype "passive"))
    )
    (net (code "11") (name "Net-(J10-Pad1)") (class "Default")
      (node (ref "J10") (pin "1") (pinfunction "1_1") (pintype "passive"))
      (node (ref "R10") (pin "1") (pinfunction "1_1") (pintype "passive"))
      (node (ref "R9") (pin "2") (pinfunction "2_2") (pintype "passive"))
    )
    (net (code "12") (name "Net-(J11-Pad1)") (class "Default")
      (node (ref "J11") (pin "1") (pinfunction "1_1") (pintype "passive"))
      (node (ref "R10") (pin "2") (pinfunction "2_2") (pintype "passive"))
    )
    (net (code "13") (name "Net-(J12-Pad1)") (class "Default")
      (node (ref "J12") (pin "1") (pinfunction "1_1") (pintype "passive"))
      (node (ref "TP1") (pin "1") (pinfunction "1_1") (pintype "passive"))
    )
    (net (code "14") (name "Net-(J13-Pad1)") (class "Default")
      (node (ref "J13") (pin "1") (pinfunction "1_1") (pintype "passive"))
      (node (ref "R12") (pin "2") (pinfunction "2_2") (pintype "passive"))
      (node (ref "TP2") (pin "1") (pinfunction "1_1") (pintype "passive"))
    )
    (net (code "15") (name "Net-(J14-Pad1)") (class "Default")
      (node (ref "J14") (pin "1") (pinfunction "1_1") (pintype "passive"))
      (node (ref "R12") (pin "1") (pinfunction "1_1") (pintype "passive"))
      (node (ref "R13") (pin "2") (pinfunction "2_2") (pintype "passive"))
    )
    (net (code "16") (name "Net-(J15-Pad1)") (class "Default")
      (node (ref "J15") (pin "1") (pinfunction "1_1") (pintype "passive"))
      (node (ref "R13") (pin "1") (pinfunction "1_1") (pintype "passive"))
      (node (ref "R14") (pin "2") (pinfunction "2_2") (pintype "passive"))
    )
    (net (code "17") (name "Net-(J16-Pad1)") (class "Default")
      (node (ref "J16") (pin "1") (pinfunction "1_1") (pintype "passive"))
      (node (ref "R14") (pin "1") (pinfunction "1_1") (pintype "passive"))
      (node (ref "R15") (pin "2") (pinfunction "2_2") (pintype "passive"))
    )
    (net (code "18") (name "Net-(J17-Pad1)") (class "Default")
      (node (ref "J17") (pin "1") (pinfunction "1_1") (pintype "passive"))
      (node (ref "R15") (pin "1") (pinfunction "1_1") (pintype "passive"))
      (node (ref "R16") (pin "2") (pinfunction "2_2") (pintype "passive"))
    )
    (net (code "19") (name "Net-(J18-Pad1)") (class "Default")
      (node (ref "J18") (pin "1") (pinfunction "1_1") (pintype "passive"))
      (node (ref "R16") (pin "1") (pinfunction "1_1") (pintype "passive"))
      (node (ref "R17") (pin "2") (pinfunction "2_2") (pintype "passive"))
    )
    (net (code "20") (name "Net-(J19-Pad1)") (class "Default")
      (node (ref "J19") (pin "1") (pinfunction "1_1") (pintype "passive"))
      (node (ref "R17") (pin "1") (pinfunction "1_1") (pintype "passive"))
      (node (ref "R18") (pin "2") (pinfunction "2_2") (pintype "passive"))
    )
    (net (code "21") (name "Net-(J20-Pad1)") (class "Default")
      (node (ref "J20") (pin "1") (pinfunction "1_1") (pintype "passive"))
      (node (ref "R18") (pin "1") (pinfunction "1_1") (pintype "passive"))
      (node (ref "R19") (pin "2") (pinfunction "2_2") (pintype "passive"))
    )
    (net (code "22") (name "Net-(J21-Pad1)") (class "Default")
      (node (ref "J21") (pin "1") (pinfunction "1_1") (pintype "passive"))
      (node (ref "R19") (pin "1") (pinfunction "1_1") (pintype "passive"))
      (node (ref "R20") (pin "2") (pinfunction "2_2") (pintype "passive"))
    )
    (net (code "23") (name "Net-(J22-Pad1)") (class "Default")
      (node (ref "J22") (pin "1") (pinfunction "1_1") (pintype "passive"))
      (node (ref "R20") (pin "1") (pinfunction "1_1") (pintype "passive"))
    )
  )
)
